# LampenSteuerung.net
KiCad netlist of a schematic drawn in EAGLE
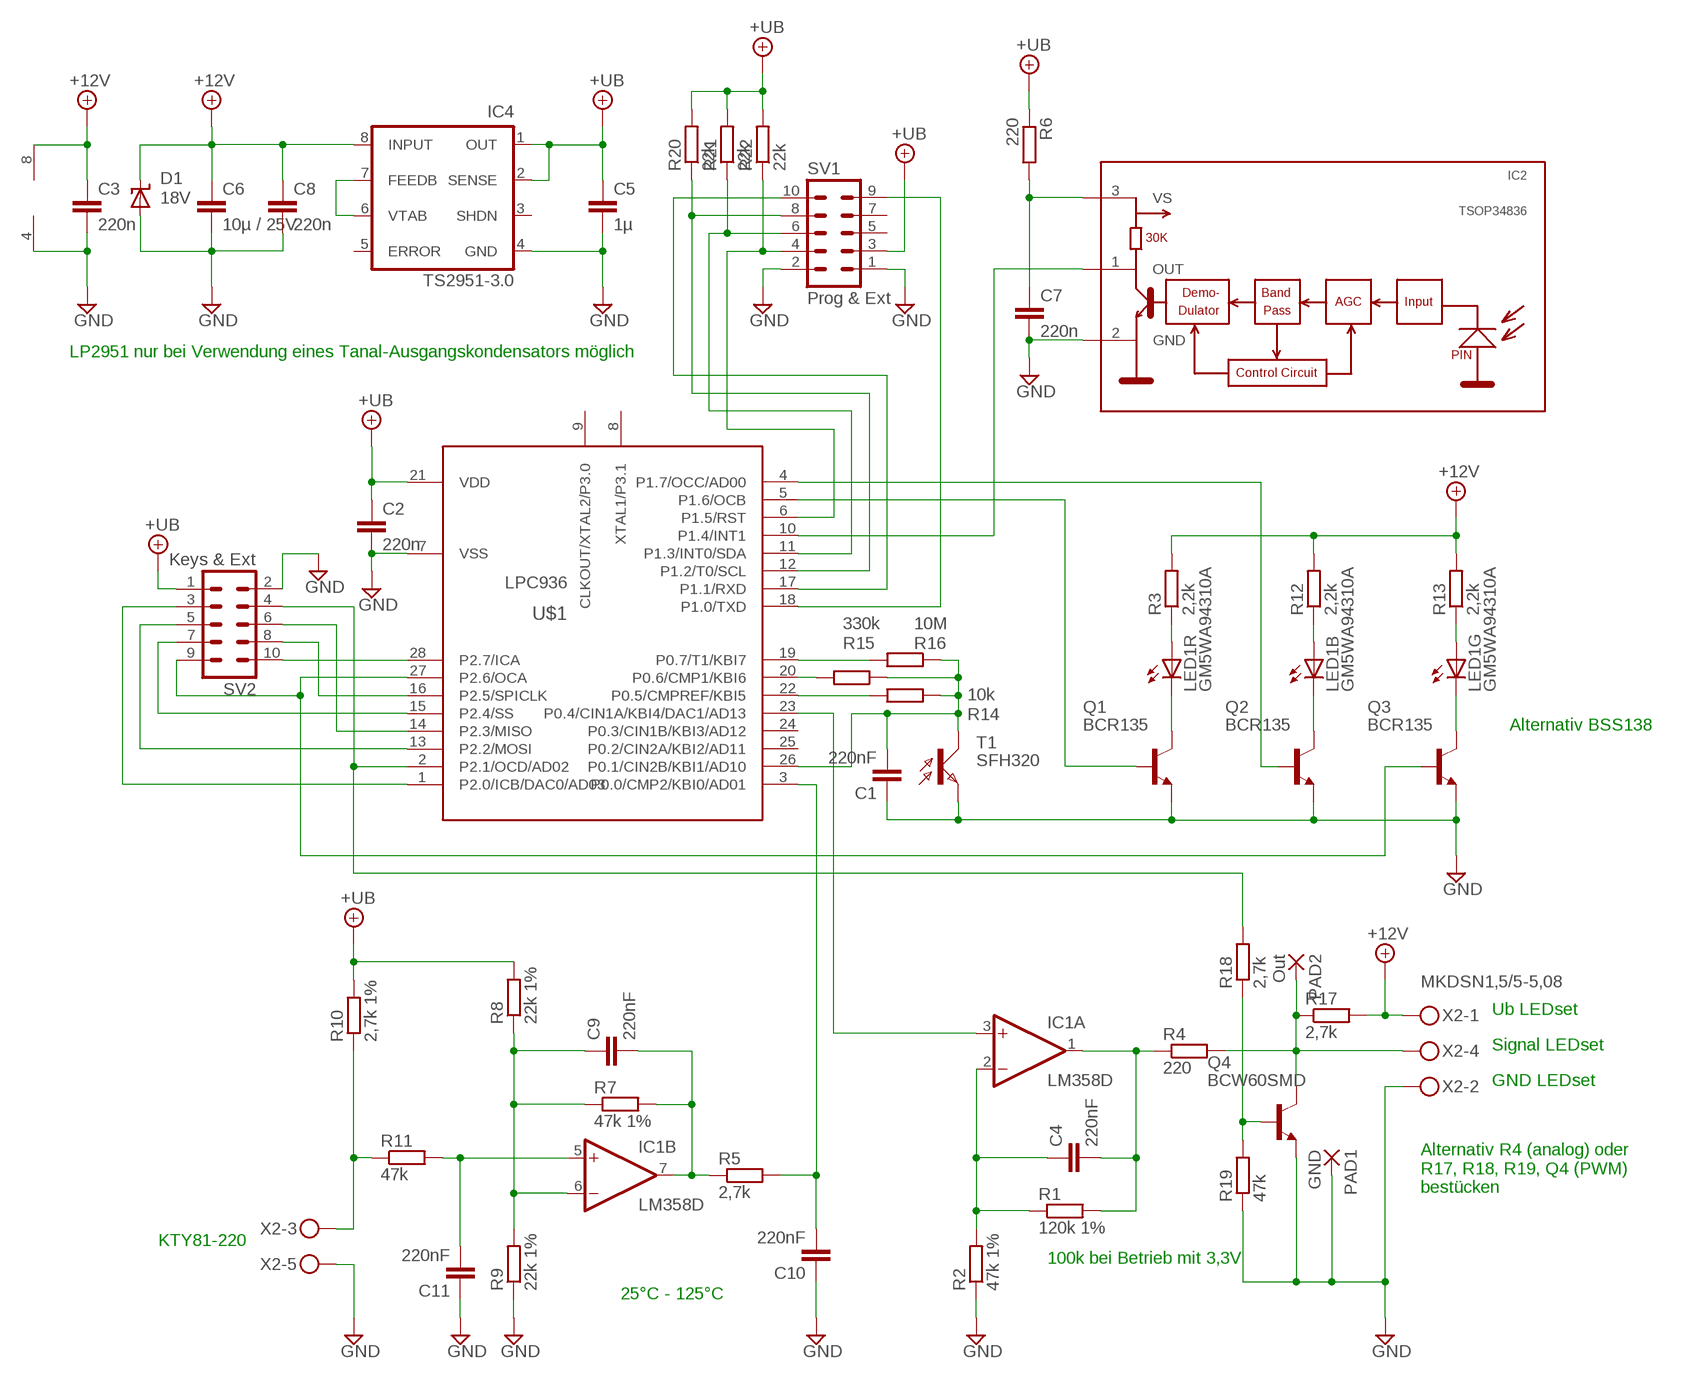
[diagram p0: schematic, sheet 1]

(export (version "E")
  (design (tool "Eeschema 10.0.6"))
  (components
    (comp (ref "C1")
      (value "220nF")
      (footprint "eagle-import:C0603")
      (libsource (lib "eagle-import") (part "C-EUC0603"))
    )
    (comp (ref "C2")
      (value "220n")
      (footprint "eagle-import:C0603")
      (libsource (lib "eagle-import") (part "C-EUC0603"))
    )
    (comp (ref "C3")
      (value "220n")
      (footprint "eagle-import:C0603")
      (libsource (lib "eagle-import") (part "C-EUC0603"))
    )
    (comp (ref "C4")
      (value "220nF")
      (footprint "eagle-import:C0603")
      (libsource (lib "eagle-import") (part "C-EUC0603"))
    )
    (comp (ref "C5")
      (value "1µ")
      (footprint "eagle-import:C0805")
      (libsource (lib "eagle-import") (part "C-EUC0805"))
    )
    (comp (ref "C6")
      (value "10µ / 25V")
      (footprint "eagle-import:C1206")
      (libsource (lib "eagle-import") (part "C-EUC1206"))
    )
    (comp (ref "C7")
      (value "220n")
      (footprint "eagle-import:C0603")
      (libsource (lib "eagle-import") (part "C-EUC0603"))
    )
    (comp (ref "C8")
      (value "220n")
      (footprint "eagle-import:C0603")
      (libsource (lib "eagle-import") (part "C-EUC0603"))
    )
    (comp (ref "C9")
      (value "220nF")
      (footprint "eagle-import:C0603")
      (libsource (lib "eagle-import") (part "C-EUC0603"))
    )
    (comp (ref "C10")
      (value "220nF")
      (footprint "eagle-import:C0603")
      (libsource (lib "eagle-import") (part "C-EUC0603"))
    )
    (comp (ref "C11")
      (value "220nF")
      (footprint "eagle-import:C0603")
      (libsource (lib "eagle-import") (part "C-EUC0603"))
    )
    (comp (ref "D1")
      (value "18V")
      (footprint "eagle-import:SMBJ")
      (libsource (lib "eagle-import") (part "SUPPRESSOR-SMBJ"))
    )
    (comp (ref "IC1")
      (value "LM358D")
      (footprint "eagle-import:SO08")
      (libsource (lib "eagle-import") (part "LM358D"))
    )
    (comp (ref "IC2")
      (value "TSOP34836")
      (footprint "eagle-import:TSOP348")
      (libsource (lib "eagle-import") (part "TSOP34836"))
    )
    (comp (ref "IC4")
      (value "TS2951-3.0")
      (footprint "eagle-import:SO-08")
      (libsource (lib "eagle-import") (part "LP2951?CM-3.0"))
    )
    (comp (ref "LED1")
      (value "GM5WA94310A")
      (footprint "eagle-import:GM5WA94310A")
      (libsource (lib "eagle-import") (part "GM5WA94310A"))
    )
    (comp (ref "PAD1")
      (value "GND")
      (footprint "eagle-import:1,6_0,8")
      (libsource (lib "eagle-import") (part "1,6/0,8"))
    )
    (comp (ref "PAD2")
      (value "Out")
      (footprint "eagle-import:1,6_0,8")
      (libsource (lib "eagle-import") (part "1,6/0,8"))
    )
    (comp (ref "Q1")
      (value "BCR135")
      (footprint "eagle-import:SOT23-BEC")
      (libsource (lib "eagle-import") (part "BCW60SMD"))
    )
    (comp (ref "Q2")
      (value "BCR135")
      (footprint "eagle-import:SOT23-BEC")
      (libsource (lib "eagle-import") (part "BCW60SMD"))
    )
    (comp (ref "Q3")
      (value "BCR135")
      (footprint "eagle-import:SOT23-BEC")
      (libsource (lib "eagle-import") (part "BCW60SMD"))
    )
    (comp (ref "Q4")
      (value "BCW60SMD")
      (footprint "eagle-import:SOT23-BEC")
      (libsource (lib "eagle-import") (part "BCW60SMD"))
    )
    (comp (ref "R1")
      (value "120k 1%")
      (footprint "eagle-import:R0805")
      (libsource (lib "eagle-import") (part "R-EU_R0805"))
    )
    (comp (ref "R2")
      (value "47k 1%")
      (footprint "eagle-import:R0805")
      (libsource (lib "eagle-import") (part "R-EU_R0805"))
    )
    (comp (ref "R3")
      (value "2,2k")
      (footprint "eagle-import:R0805")
      (libsource (lib "eagle-import") (part "R-EU_R0805"))
    )
    (comp (ref "R4")
      (value "220")
      (footprint "eagle-import:R0805")
      (libsource (lib "eagle-import") (part "R-EU_R0805"))
    )
    (comp (ref "R5")
      (value "2,7k")
      (footprint "eagle-import:R0805")
      (libsource (lib "eagle-import") (part "R-EU_R0805"))
    )
    (comp (ref "R6")
      (value "220")
      (footprint "eagle-import:R0805")
      (libsource (lib "eagle-import") (part "R-EU_R0805"))
    )
    (comp (ref "R7")
      (value "47k 1%")
      (footprint "eagle-import:R0805")
      (libsource (lib "eagle-import") (part "R-EU_R0805"))
    )
    (comp (ref "R8")
      (value "22k 1%")
      (footprint "eagle-import:R0805")
      (libsource (lib "eagle-import") (part "R-EU_R0805"))
    )
    (comp (ref "R9")
      (value "22k 1%")
      (footprint "eagle-import:R0805")
      (libsource (lib "eagle-import") (part "R-EU_R0805"))
    )
    (comp (ref "R10")
      (value "2,7k 1%")
      (footprint "eagle-import:R0805")
      (libsource (lib "eagle-import") (part "R-EU_R0805"))
    )
    (comp (ref "R11")
      (value "47k")
      (footprint "eagle-import:R0805")
      (libsource (lib "eagle-import") (part "R-EU_R0805"))
    )
    (comp (ref "R12")
      (value "2,2k")
      (footprint "eagle-import:R0805")
      (libsource (lib "eagle-import") (part "R-EU_R0805"))
    )
    (comp (ref "R13")
      (value "2,2k")
      (footprint "eagle-import:R0805")
      (libsource (lib "eagle-import") (part "R-EU_R0805"))
    )
    (comp (ref "R14")
      (value "10k")
      (footprint "eagle-import:R0805")
      (libsource (lib "eagle-import") (part "R-EU_R0805"))
    )
    (comp (ref "R15")
      (value "330k")
      (footprint "eagle-import:R0805")
      (libsource (lib "eagle-import") (part "R-EU_R0805"))
    )
    (comp (ref "R16")
      (value "10M")
      (footprint "eagle-import:R0805")
      (libsource (lib "eagle-import") (part "R-EU_R0805"))
    )
    (comp (ref "R17")
      (value "2,7k")
      (footprint "eagle-import:R0805")
      (libsource (lib "eagle-import") (part "R-EU_R0805"))
    )
    (comp (ref "R18")
      (value "2,7k")
      (footprint "eagle-import:R0805")
      (libsource (lib "eagle-import") (part "R-EU_R0805"))
    )
    (comp (ref "R19")
      (value "47k")
      (footprint "eagle-import:R0805")
      (libsource (lib "eagle-import") (part "R-EU_R0805"))
    )
    (comp (ref "R20")
      (value "22k")
      (footprint "eagle-import:R0805")
      (libsource (lib "eagle-import") (part "R-EU_R0805"))
    )
    (comp (ref "R21")
      (value "22k")
      (footprint "eagle-import:R0805")
      (libsource (lib "eagle-import") (part "R-EU_R0805"))
    )
    (comp (ref "R22")
      (value "22k")
      (footprint "eagle-import:R0805")
      (libsource (lib "eagle-import") (part "R-EU_R0805"))
    )
    (comp (ref "SV1")
      (value "Prog & Ext")
      (footprint "eagle-import:MA05-2")
      (libsource (lib "eagle-import") (part "MA05-2"))
    )
    (comp (ref "SV2")
      (value "Keys & Ext")
      (footprint "eagle-import:MA05-2")
      (libsource (lib "eagle-import") (part "MA05-2"))
    )
    (comp (ref "T1")
      (value "SFH320")
      (footprint "eagle-import:PLCC2")
      (libsource (lib "eagle-import") (part "SFH320"))
    )
    (comp (ref "U$1")
      (value "LPC936")
      (footprint "eagle-import:TSSOP28")
      (libsource (lib "eagle-import") (part "LPC936"))
    )
    (comp (ref "X2")
      (value "MKDSN1,5/5-5,08")
      (footprint "eagle-import:MKDSN1,5_5-5,08")
      (fields (field (name "MPN") "SMKDSN1,5/5-5,08"))
      (libsource (lib "eagle-import") (part "MKDSN1,5/5-5,08"))
    )
  )
  (nets
    (net (code "1") (name "+12V") (class "Default")
      (node (ref "C3") (pin "1") (pinfunction "1_1") (pintype "passive"))
      (node (ref "C6") (pin "1") (pinfunction "1_1") (pintype "passive"))
      (node (ref "C8") (pin "1") (pinfunction "1_1") (pintype "passive"))
      (node (ref "D1") (pin "C") (pinfunction "C_C") (pintype "passive"))
      (node (ref "IC1") (pin "8") (pinfunction "V+_8") (pintype "power_in"))
      (node (ref "IC4") (pin "8") (pinfunction "INPUT_8") (pintype "passive"))
      (node (ref "R12") (pin "2") (pinfunction "2_2") (pintype "passive"))
      (node (ref "R13") (pin "2") (pinfunction "2_2") (pintype "passive"))
      (node (ref "R17") (pin "2") (pinfunction "2_2") (pintype "passive"))
      (node (ref "R3") (pin "2") (pinfunction "2_2") (pintype "passive"))
      (node (ref "X2") (pin "1") (pinfunction "KL_1") (pintype "passive"))
    )
    (net (code "2") (name "+UB") (class "Default")
      (node (ref "C2") (pin "1") (pinfunction "1_1") (pintype "passive"))
      (node (ref "C5") (pin "1") (pinfunction "1_1") (pintype "passive"))
      (node (ref "IC4") (pin "1") (pinfunction "OUT_1") (pintype "output"))
      (node (ref "IC4") (pin "2") (pinfunction "SENSE_2") (pintype "input"))
      (node (ref "R10") (pin "2") (pinfunction "2_2") (pintype "passive"))
      (node (ref "R20") (pin "2") (pinfunction "2_2") (pintype "passive"))
      (node (ref "R21") (pin "2") (pinfunction "2_2") (pintype "passive"))
      (node (ref "R22") (pin "2") (pinfunction "2_2") (pintype "passive"))
      (node (ref "R6") (pin "1") (pinfunction "1_1") (pintype "passive"))
      (node (ref "R8") (pin "2") (pinfunction "2_2") (pintype "passive"))
      (node (ref "SV1") (pin "3") (pinfunction "3_3") (pintype "passive"))
      (node (ref "SV2") (pin "1") (pinfunction "1_1") (pintype "passive"))
      (node (ref "U$1") (pin "21") (pinfunction "VDD_21") (pintype "bidirectional"))
    )
    (net (code "3") (name "GND") (class "Default")
      (node (ref "C1") (pin "1") (pinfunction "1_1") (pintype "passive"))
      (node (ref "C10") (pin "1") (pinfunction "1_1") (pintype "passive"))
      (node (ref "C11") (pin "1") (pinfunction "1_1") (pintype "passive"))
      (node (ref "C2") (pin "2") (pinfunction "2_2") (pintype "passive"))
      (node (ref "C3") (pin "2") (pinfunction "2_2") (pintype "passive"))
      (node (ref "C5") (pin "2") (pinfunction "2_2") (pintype "passive"))
      (node (ref "C6") (pin "2") (pinfunction "2_2") (pintype "passive"))
      (node (ref "C7") (pin "2") (pinfunction "2_2") (pintype "passive"))
      (node (ref "C8") (pin "2") (pinfunction "2_2") (pintype "passive"))
      (node (ref "D1") (pin "A") (pinfunction "A_A") (pintype "passive"))
      (node (ref "IC1") (pin "4") (pinfunction "V-_4") (pintype "power_in"))
      (node (ref "IC2") (pin "2") (pinfunction "GND_2") (pintype "power_in"))
      (node (ref "IC4") (pin "4") (pinfunction "GND_4") (pintype "power_in"))
      (node (ref "PAD1") (pin "1") (pinfunction "P_1") (pintype "passive"))
      (node (ref "Q1") (pin "E") (pinfunction "E_E") (pintype "passive"))
      (node (ref "Q2") (pin "E") (pinfunction "E_E") (pintype "passive"))
      (node (ref "Q3") (pin "E") (pinfunction "E_E") (pintype "passive"))
      (node (ref "Q4") (pin "E") (pinfunction "E_E") (pintype "passive"))
      (node (ref "R19") (pin "1") (pinfunction "1_1") (pintype "passive"))
      (node (ref "R2") (pin "1") (pinfunction "1_1") (pintype "passive"))
      (node (ref "R9") (pin "1") (pinfunction "1_1") (pintype "passive"))
      (node (ref "SV1") (pin "1") (pinfunction "1_1") (pintype "passive"))
      (node (ref "SV1") (pin "2") (pinfunction "2_2") (pintype "passive"))
      (node (ref "SV2") (pin "2") (pinfunction "2_2") (pintype "passive"))
      (node (ref "T1") (pin "C") (pinfunction "E_C") (pintype "passive"))
      (node (ref "U$1") (pin "7") (pinfunction "VSS_7") (pintype "bidirectional"))
      (node (ref "X2") (pin "2") (pinfunction "KL_2") (pintype "passive"))
      (node (ref "X2") (pin "5") (pinfunction "KL_5") (pintype "passive"))
    )
    (net (code "4") (name "Net-(IC1A-+IN)") (class "Default")
      (node (ref "IC1") (pin "3") (pinfunction "+IN_3") (pintype "input"))
      (node (ref "U$1") (pin "23") (pinfunction "P0.4/CIN1A/KBI4/DAC1/AD13_23") (pintype "bidirectional"))
    )
    (net (code "5") (name "Net-(IC1A--IN)") (class "Default")
      (node (ref "C4") (pin "1") (pinfunction "1_1") (pintype "passive"))
      (node (ref "IC1") (pin "2") (pinfunction "-IN_2") (pintype "input"))
      (node (ref "R1") (pin "1") (pinfunction "1_1") (pintype "passive"))
      (node (ref "R2") (pin "2") (pinfunction "2_2") (pintype "passive"))
    )
    (net (code "6") (name "Net-(IC1A-OUT)") (class "Default")
      (node (ref "C4") (pin "2") (pinfunction "2_2") (pintype "passive"))
      (node (ref "IC1") (pin "1") (pinfunction "OUT_1") (pintype "output"))
      (node (ref "R1") (pin "2") (pinfunction "2_2") (pintype "passive"))
      (node (ref "R4") (pin "1") (pinfunction "1_1") (pintype "passive"))
    )
    (net (code "7") (name "Net-(IC1B-+IN)") (class "Default")
      (node (ref "C11") (pin "2") (pinfunction "2_2") (pintype "passive"))
      (node (ref "IC1") (pin "5") (pinfunction "+IN_5") (pintype "input"))
      (node (ref "R11") (pin "2") (pinfunction "2_2") (pintype "passive"))
    )
    (net (code "8") (name "Net-(IC1B--IN)") (class "Default")
      (node (ref "C9") (pin "1") (pinfunction "1_1") (pintype "passive"))
      (node (ref "IC1") (pin "6") (pinfunction "-IN_6") (pintype "input"))
      (node (ref "R7") (pin "1") (pinfunction "1_1") (pintype "passive"))
      (node (ref "R8") (pin "1") (pinfunction "1_1") (pintype "passive"))
      (node (ref "R9") (pin "2") (pinfunction "2_2") (pintype "passive"))
    )
    (net (code "9") (name "Net-(IC1B-OUT)") (class "Default")
      (node (ref "C9") (pin "2") (pinfunction "2_2") (pintype "passive"))
      (node (ref "IC1") (pin "7") (pinfunction "OUT_7") (pintype "output"))
      (node (ref "R5") (pin "1") (pinfunction "1_1") (pintype "passive"))
      (node (ref "R7") (pin "2") (pinfunction "2_2") (pintype "passive"))
    )
    (net (code "10") (name "Net-(IC2-OUT)") (class "Default")
      (node (ref "IC2") (pin "1") (pinfunction "OUT_1") (pintype "output"))
      (node (ref "U$1") (pin "10") (pinfunction "P1.4/INT1_10") (pintype "bidirectional"))
    )
    (net (code "11") (name "Net-(IC2-VS)") (class "Default")
      (node (ref "C7") (pin "1") (pinfunction "1_1") (pintype "passive"))
      (node (ref "IC2") (pin "3") (pinfunction "VS_3") (pintype "power_in"))
      (node (ref "R6") (pin "2") (pinfunction "2_2") (pintype "passive"))
    )
    (net (code "12") (name "Net-(IC4-FEEDB)") (class "Default")
      (node (ref "IC4") (pin "6") (pinfunction "VTAB_6") (pintype "input"))
      (node (ref "IC4") (pin "7") (pinfunction "FEEDB_7") (pintype "output"))
    )
    (net (code "13") (name "Net-(LED1A-A)") (class "Default")
      (node (ref "LED1") (pin "1") (pinfunction "A_1") (pintype "passive"))
      (node (ref "R12") (pin "1") (pinfunction "1_1") (pintype "passive"))
    )
    (net (code "14") (name "Net-(LED1A-C)") (class "Default")
      (node (ref "LED1") (pin "6") (pinfunction "C_6") (pintype "passive"))
      (node (ref "Q2") (pin "C") (pinfunction "C_C") (pintype "passive"))
    )
    (net (code "15") (name "Net-(LED1B-A)") (class "Default")
      (node (ref "LED1") (pin "3") (pinfunction "A_3") (pintype "passive"))
      (node (ref "R13") (pin "1") (pinfunction "1_1") (pintype "passive"))
    )
    (net (code "16") (name "Net-(LED1B-C)") (class "Default")
      (node (ref "LED1") (pin "4") (pinfunction "C_4") (pintype "passive"))
      (node (ref "Q3") (pin "C") (pinfunction "C_C") (pintype "passive"))
    )
    (net (code "17") (name "Net-(LED1C-A)") (class "Default")
      (node (ref "LED1") (pin "2") (pinfunction "A_2") (pintype "passive"))
      (node (ref "R3") (pin "1") (pinfunction "1_1") (pintype "passive"))
    )
    (net (code "18") (name "Net-(LED1C-C)") (class "Default")
      (node (ref "LED1") (pin "5") (pinfunction "C_5") (pintype "passive"))
      (node (ref "Q1") (pin "C") (pinfunction "C_C") (pintype "passive"))
    )
    (net (code "19") (name "Net-(PAD2-P)") (class "Default")
      (node (ref "PAD2") (pin "1") (pinfunction "P_1") (pintype "passive"))
      (node (ref "Q4") (pin "C") (pinfunction "C_C") (pintype "passive"))
      (node (ref "R17") (pin "1") (pinfunction "1_1") (pintype "passive"))
      (node (ref "R4") (pin "2") (pinfunction "2_2") (pintype "passive"))
      (node (ref "X2") (pin "4") (pinfunction "KL_4") (pintype "passive"))
    )
    (net (code "20") (name "Net-(Q4-PadB)") (class "Default")
      (node (ref "Q4") (pin "B") (pinfunction "B_B") (pintype "passive"))
      (node (ref "R18") (pin "1") (pinfunction "1_1") (pintype "passive"))
      (node (ref "R19") (pin "2") (pinfunction "2_2") (pintype "passive"))
    )
    (net (code "21") (name "Net-(T1-C)") (class "Default")
      (node (ref "C1") (pin "2") (pinfunction "2_2") (pintype "passive"))
      (node (ref "R14") (pin "1") (pinfunction "1_1") (pintype "passive"))
      (node (ref "R15") (pin "1") (pinfunction "1_1") (pintype "passive"))
      (node (ref "R16") (pin "1") (pinfunction "1_1") (pintype "passive"))
      (node (ref "T1") (pin "A") (pinfunction "C_A") (pintype "passive"))
      (node (ref "U$1") (pin "26") (pinfunction "P0.1/CIN2B/KBI1/AD10_26") (pintype "bidirectional"))
    )
    (net (code "22") (name "Net-(U$1-P0.0{slash}CMP2{slash}KBI0{slash}AD01)") (class "Default")
      (node (ref "C10") (pin "2") (pinfunction "2_2") (pintype "passive"))
      (node (ref "R5") (pin "2") (pinfunction "2_2") (pintype "passive"))
      (node (ref "U$1") (pin "3") (pinfunction "P0.0/CMP2/KBI0/AD01_3") (pintype "bidirectional"))
    )
    (net (code "23") (name "Net-(U$1-P0.5{slash}CMPREF{slash}KBI5)") (class "Default")
      (node (ref "R14") (pin "2") (pinfunction "2_2") (pintype "passive"))
      (node (ref "U$1") (pin "22") (pinfunction "P0.5/CMPREF/KBI5_22") (pintype "bidirectional"))
    )
    (net (code "24") (name "Net-(U$1-P0.6{slash}CMP1{slash}KBI6)") (class "Default")
      (node (ref "R15") (pin "2") (pinfunction "2_2") (pintype "passive"))
      (node (ref "U$1") (pin "20") (pinfunction "P0.6/CMP1/KBI6_20") (pintype "bidirectional"))
    )
    (net (code "25") (name "Net-(U$1-P0.7{slash}T1{slash}KBI7)") (class "Default")
      (node (ref "R16") (pin "2") (pinfunction "2_2") (pintype "passive"))
      (node (ref "U$1") (pin "19") (pinfunction "P0.7/T1/KBI7_19") (pintype "bidirectional"))
    )
    (net (code "26") (name "Net-(U$1-P1.0{slash}TXD)") (class "Default")
      (node (ref "SV1") (pin "9") (pinfunction "9_9") (pintype "passive"))
      (node (ref "U$1") (pin "18") (pinfunction "P1.0/TXD_18") (pintype "bidirectional"))
    )
    (net (code "27") (name "Net-(U$1-P1.1{slash}RXD)") (class "Default")
      (node (ref "SV1") (pin "10") (pinfunction "10_10") (pintype "passive"))
      (node (ref "U$1") (pin "17") (pinfunction "P1.1/RXD_17") (pintype "bidirectional"))
    )
    (net (code "28") (name "Net-(U$1-P1.2{slash}T0{slash}SCL)") (class "Default")
      (node (ref "R20") (pin "1") (pinfunction "1_1") (pintype "passive"))
      (node (ref "SV1") (pin "8") (pinfunction "8_8") (pintype "passive"))
      (node (ref "U$1") (pin "12") (pinfunction "P1.2/T0/SCL_12") (pintype "bidirectional"))
    )
    (net (code "29") (name "Net-(U$1-P1.3{slash}INT0{slash}SDA)") (class "Default")
      (node (ref "R21") (pin "1") (pinfunction "1_1") (pintype "passive"))
      (node (ref "SV1") (pin "6") (pinfunction "6_6") (pintype "passive"))
      (node (ref "U$1") (pin "11") (pinfunction "P1.3/INT0/SDA_11") (pintype "bidirectional"))
    )
    (net (code "30") (name "Net-(U$1-P1.5{slash}RST)") (class "Default")
      (node (ref "R22") (pin "1") (pinfunction "1_1") (pintype "passive"))
      (node (ref "SV1") (pin "4") (pinfunction "4_4") (pintype "passive"))
      (node (ref "U$1") (pin "6") (pinfunction "P1.5/RST_6") (pintype "bidirectional"))
    )
    (net (code "31") (name "Net-(U$1-P1.6{slash}OCB)") (class "Default")
      (node (ref "Q1") (pin "B") (pinfunction "B_B") (pintype "passive"))
      (node (ref "U$1") (pin "5") (pinfunction "P1.6/OCB_5") (pintype "bidirectional"))
    )
    (net (code "32") (name "Net-(U$1-P1.7{slash}OCC{slash}AD00)") (class "Default")
      (node (ref "Q2") (pin "B") (pinfunction "B_B") (pintype "passive"))
      (node (ref "U$1") (pin "4") (pinfunction "P1.7/OCC/AD00_4") (pintype "bidirectional"))
    )
    (net (code "33") (name "Net-(U$1-P2.0{slash}ICB{slash}DAC0{slash}AD03)") (class "Default")
      (node (ref "SV2") (pin "3") (pinfunction "3_3") (pintype "passive"))
      (node (ref "U$1") (pin "1") (pinfunction "P2.0/ICB/DAC0/AD03_1") (pintype "bidirectional"))
    )
    (net (code "34") (name "Net-(U$1-P2.1{slash}OCD{slash}AD02)") (class "Default")
      (node (ref "R18") (pin "2") (pinfunction "2_2") (pintype "passive"))
      (node (ref "SV2") (pin "4") (pinfunction "4_4") (pintype "passive"))
      (node (ref "U$1") (pin "2") (pinfunction "P2.1/OCD/AD02_2") (pintype "bidirectional"))
    )
    (net (code "35") (name "Net-(U$1-P2.2{slash}MOSI)") (class "Default")
      (node (ref "SV2") (pin "5") (pinfunction "5_5") (pintype "passive"))
      (node (ref "U$1") (pin "13") (pinfunction "P2.2/MOSI_13") (pintype "bidirectional"))
    )
    (net (code "36") (name "Net-(U$1-P2.3{slash}MISO)") (class "Default")
      (node (ref "SV2") (pin "6") (pinfunction "6_6") (pintype "passive"))
      (node (ref "U$1") (pin "14") (pinfunction "P2.3/MISO_14") (pintype "bidirectional"))
    )
    (net (code "37") (name "Net-(U$1-P2.4{slash}SS)") (class "Default")
      (node (ref "SV2") (pin "7") (pinfunction "7_7") (pintype "passive"))
      (node (ref "U$1") (pin "15") (pinfunction "P2.4/SS_15") (pintype "bidirectional"))
    )
    (net (code "38") (name "Net-(U$1-P2.5{slash}SPICLK)") (class "Default")
      (node (ref "SV2") (pin "8") (pinfunction "8_8") (pintype "passive"))
      (node (ref "U$1") (pin "16") (pinfunction "P2.5/SPICLK_16") (pintype "bidirectional"))
    )
    (net (code "39") (name "Net-(U$1-P2.6{slash}OCA)") (class "Default")
      (node (ref "Q3") (pin "B") (pinfunction "B_B") (pintype "passive"))
      (node (ref "SV2") (pin "9") (pinfunction "9_9") (pintype "passive"))
      (node (ref "U$1") (pin "27") (pinfunction "P2.6/OCA_27") (pintype "bidirectional"))
    )
    (net (code "40") (name "Net-(U$1-P2.7{slash}ICA)") (class "Default")
      (node (ref "SV2") (pin "10") (pinfunction "10_10") (pintype "passive"))
      (node (ref "U$1") (pin "28") (pinfunction "P2.7/ICA_28") (pintype "bidirectional"))
    )
    (net (code "41") (name "Net-(X2C-KL)") (class "Default")
      (node (ref "R10") (pin "1") (pinfunction "1_1") (pintype "passive"))
      (node (ref "R11") (pin "1") (pinfunction "1_1") (pintype "passive"))
      (node (ref "X2") (pin "3") (pinfunction "KL_3") (pintype "passive"))
    )
    (net (code "42") (name "unconnected-(IC4-ERROR-Pad5)") (class "Default")
      (node (ref "IC4") (pin "5") (pinfunction "ERROR_5") (pintype "output"))
    )
    (net (code "43") (name "unconnected-(IC4-SHDN-Pad3)") (class "Default")
      (node (ref "IC4") (pin "3") (pinfunction "SHDN_3") (pintype "input"))
    )
    (net (code "44") (name "unconnected-(SV1-Pad5)") (class "Default")
      (node (ref "SV1") (pin "5") (pinfunction "5_5") (pintype "passive"))
    )
    (net (code "45") (name "unconnected-(SV1-Pad7)") (class "Default")
      (node (ref "SV1") (pin "7") (pinfunction "7_7") (pintype "passive"))
    )
    (net (code "46") (name "unconnected-(U$1-CLKOUT{slash}XTAL2{slash}P3.0-Pad9)") (class "Default")
      (node (ref "U$1") (pin "9") (pinfunction "CLKOUT/XTAL2/P3.0_9") (pintype "bidirectional"))
    )
    (net (code "47") (name "unconnected-(U$1-P0.2{slash}CIN2A{slash}KBI2{slash}AD11-Pad25)") (class "Default")
      (node (ref "U$1") (pin "25") (pinfunction "P0.2/CIN2A/KBI2/AD11_25") (pintype "bidirectional"))
    )
    (net (code "48") (name "unconnected-(U$1-P0.3{slash}CIN1B{slash}KBI3{slash}AD12-Pad24)") (class "Default")
      (node (ref "U$1") (pin "24") (pinfunction "P0.3/CIN1B/KBI3/AD12_24") (pintype "bidirectional"))
    )
    (net (code "49") (name "unconnected-(U$1-XTAL1{slash}P3.1-Pad8)") (class "Default")
      (node (ref "U$1") (pin "8") (pinfunction "XTAL1/P3.1_8") (pintype "bidirectional"))
    )
  )
)
